# DAC.net
KiCad netlist of a schematic drawn in Altium Designer
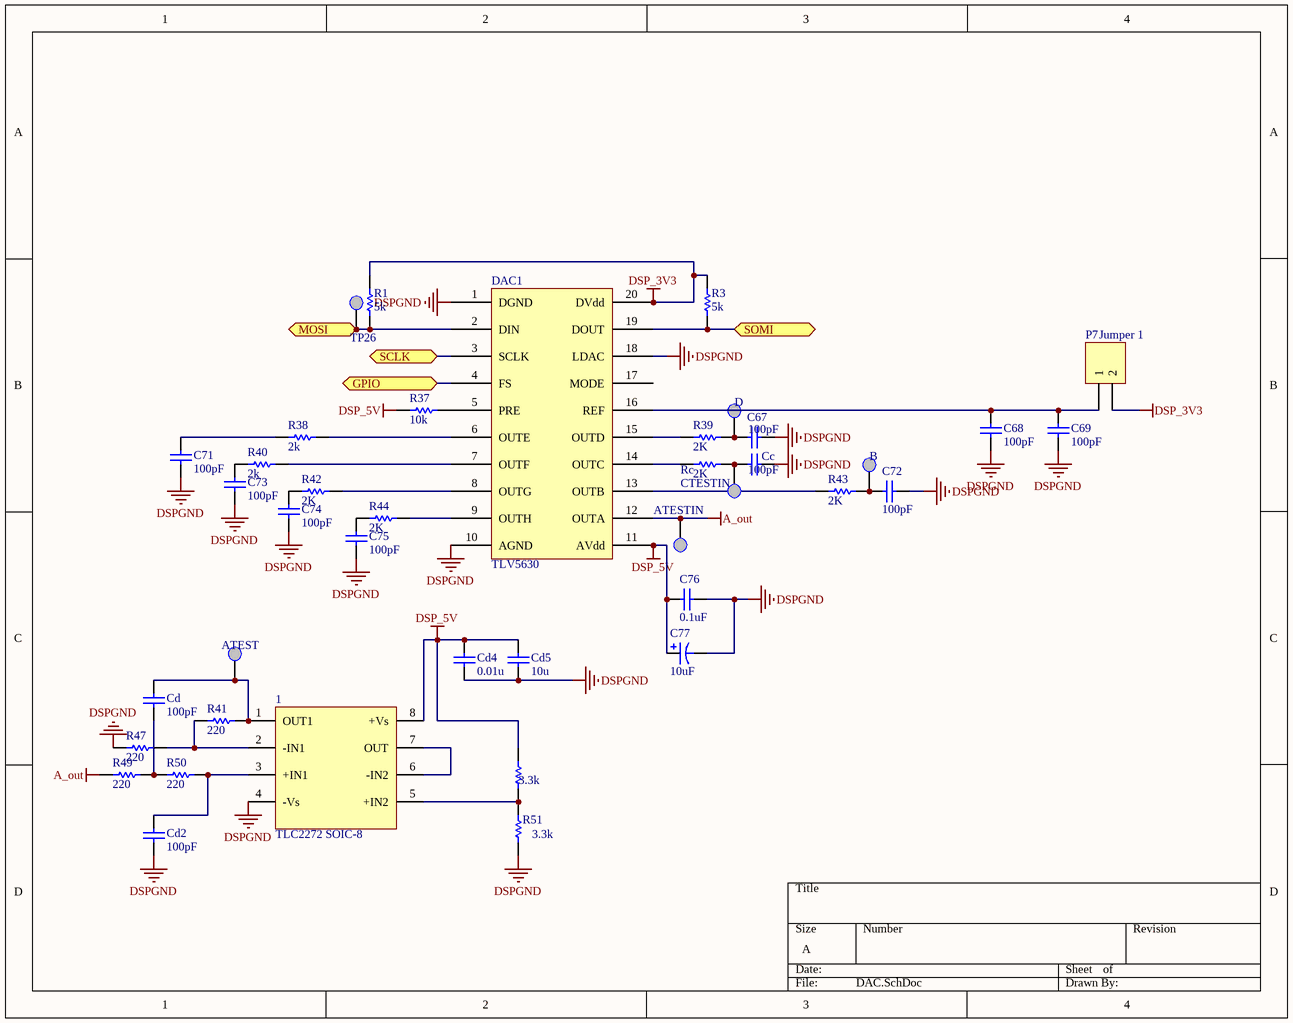
[diagram p0: DAC.SchDoc]

(export (version "E")
  (design (tool "Eeschema 10.0.6"))
  (components
    (comp (ref "1")
      (value "TLC2272 SOIC-8")
      (footprint "AD8056")
      (libsource (lib "control Board") (part "AD8056"))
    )
    (comp (ref "3.3k")
      (value "Res1")
      (footprint "0805 RES")
      (description "Resistor")
      (fields (field (name "PUBLISHER") "Altium Limited"))
      (libsource (lib "control Board") (part "Res1"))
    )
    (comp (ref "ATEST")
      (value "Test point")
      (footprint "Test Point")
      (libsource (lib "control Board") (part "Test point"))
    )
    (comp (ref "ATESTIN")
      (value "Test point")
      (footprint "Test Point")
      (libsource (lib "control Board") (part "Test point"))
    )
    (comp (ref "B")
      (value "Test point")
      (footprint "Test Point")
      (libsource (lib "control Board") (part "Test point"))
    )
    (comp (ref "C67")
      (value "100pF")
      (footprint "Capacitor 0805")
      (description "Capacitor")
      (fields (field (name "Comment") "Cap") (field (name "PUBLISHER") "Altium Limited"))
      (libsource (lib "Miscellaneous Devices") (part "Cap"))
    )
    (comp (ref "C68")
      (value "100pF")
      (footprint "Capacitor 0805")
      (description "Capacitor")
      (fields (field (name "Comment") "Cap") (field (name "PUBLISHER") "Altium Limited"))
      (libsource (lib "Miscellaneous Devices") (part "Cap"))
    )
    (comp (ref "C69")
      (value "100pF")
      (footprint "Capacitor 0805")
      (description "Capacitor")
      (fields (field (name "Comment") "Cap") (field (name "PUBLISHER") "Altium Limited"))
      (libsource (lib "Miscellaneous Devices") (part "Cap"))
    )
    (comp (ref "C71")
      (value "100pF")
      (footprint "Capacitor 0805")
      (description "Capacitor")
      (fields (field (name "Comment") "Cap") (field (name "PUBLISHER") "Altium Limited"))
      (libsource (lib "Miscellaneous Devices") (part "Cap"))
    )
    (comp (ref "C72")
      (value "100pF")
      (footprint "Capacitor 0805")
      (description "Capacitor")
      (fields (field (name "Comment") "Cap") (field (name "PUBLISHER") "Altium Limited"))
      (libsource (lib "Miscellaneous Devices") (part "Cap"))
    )
    (comp (ref "C73")
      (value "100pF")
      (footprint "Capacitor 0805")
      (description "Capacitor")
      (fields (field (name "Comment") "Cap") (field (name "PUBLISHER") "Altium Limited"))
      (libsource (lib "Miscellaneous Devices") (part "Cap"))
    )
    (comp (ref "C74")
      (value "100pF")
      (footprint "Capacitor 0805")
      (description "Capacitor")
      (fields (field (name "Comment") "Cap") (field (name "PUBLISHER") "Altium Limited"))
      (libsource (lib "Miscellaneous Devices") (part "Cap"))
    )
    (comp (ref "C75")
      (value "100pF")
      (footprint "Capacitor 0805")
      (description "Capacitor")
      (fields (field (name "Comment") "Cap") (field (name "PUBLISHER") "Altium Limited"))
      (libsource (lib "Miscellaneous Devices") (part "Cap"))
    )
    (comp (ref "C76")
      (value "0.1uF")
      (footprint "Capacitor 0805")
      (description "Capacitor")
      (fields (field (name "Comment") "Cap") (field (name "PUBLISHER") "Altium Limited"))
      (libsource (lib "Miscellaneous Devices") (part "Cap"))
    )
    (comp (ref "C77")
      (value "10uF")
      (footprint "Cap Tantal 3216")
      (description "Polarized Capacitor (Radial)")
      (fields
        (field (name "Comment") "Tantalium/T520A226M006ATE090")
        (field (name "PUBLISHER") "Altium Limited")
      )
      (libsource (lib "Miscellaneous Devices") (part "Cap Pol1"))
    )
    (comp (ref "Cc")
      (value "100pF")
      (footprint "Capacitor 0805")
      (description "Capacitor")
      (fields (field (name "Comment") "Cap") (field (name "PUBLISHER") "Altium Limited"))
      (libsource (lib "Miscellaneous Devices") (part "Cap"))
    )
    (comp (ref "Cd")
      (value "100pF")
      (footprint "Capacitor 0805")
      (description "Capacitor")
      (fields (field (name "Comment") "Cap") (field (name "PUBLISHER") "Altium Limited"))
      (libsource (lib "Miscellaneous Devices") (part "Cap"))
    )
    (comp (ref "Cd2")
      (value "100pF")
      (footprint "Capacitor 0805")
      (description "Capacitor")
      (fields (field (name "Comment") "Cap") (field (name "PUBLISHER") "Altium Limited"))
      (libsource (lib "Miscellaneous Devices") (part "Cap"))
    )
    (comp (ref "Cd4")
      (value "0.01u")
      (footprint "Capacitor 0805")
      (description "Capacitor")
      (fields (field (name "Comment") "Cap") (field (name "PUBLISHER") "Altium Limited"))
      (libsource (lib "Miscellaneous Devices") (part "Cap"))
    )
    (comp (ref "Cd5")
      (value "10u")
      (footprint "Capacitor 0805")
      (description "Capacitor")
      (fields (field (name "Comment") "Cap") (field (name "PUBLISHER") "Altium Limited"))
      (libsource (lib "Miscellaneous Devices") (part "Cap"))
    )
    (comp (ref "CTESTIN")
      (value "Test point")
      (footprint "Test Point")
      (libsource (lib "control Board") (part "Test point"))
    )
    (comp (ref "D")
      (value "Test point")
      (footprint "Test Point")
      (libsource (lib "control Board") (part "Test point"))
    )
    (comp (ref "DAC1")
      (value "TLV5630")
      (footprint "TLV5630")
      (libsource (lib "control Board") (part "TLV5630"))
    )
    (comp (ref "P7")
      (value "Jumper 1")
      (footprint "HDR1X2")
      (description "Header, 2-Pin")
      (fields (field (name "PUBLISHER") "Altium Limited"))
      (libsource (lib "Miscellaneous Connectors") (part "Header 2"))
    )
    (comp (ref "R1")
      (value "5k")
      (footprint "0805 RES")
      (description "Resistor")
      (fields (field (name "Comment") "Res1") (field (name "PUBLISHER") "Altium Limited"))
      (libsource (lib "control Board") (part "Res1"))
    )
    (comp (ref "R3")
      (value "5k")
      (footprint "0805 RES")
      (description "Resistor")
      (fields (field (name "Comment") "Res1") (field (name "PUBLISHER") "Altium Limited"))
      (libsource (lib "control Board") (part "Res1"))
    )
    (comp (ref "R37")
      (value "10k")
      (footprint "0805 RES")
      (description "Resistor")
      (fields (field (name "Comment") "Res1") (field (name "PUBLISHER") "Altium Limited"))
      (libsource (lib "control Board") (part "Res1"))
    )
    (comp (ref "R38")
      (value "2k")
      (footprint "0805 RES")
      (description "Resistor")
      (fields (field (name "Comment") "Res1") (field (name "PUBLISHER") "Altium Limited"))
      (libsource (lib "control Board") (part "Res1"))
    )
    (comp (ref "R39")
      (value "2K")
      (footprint "0805 RES")
      (description "Resistor")
      (fields (field (name "Comment") "Res1") (field (name "PUBLISHER") "Altium Limited"))
      (libsource (lib "control Board") (part "Res1"))
    )
    (comp (ref "R40")
      (value "2k")
      (footprint "0805 RES")
      (description "Resistor")
      (fields (field (name "Comment") "Res1") (field (name "PUBLISHER") "Altium Limited"))
      (libsource (lib "control Board") (part "Res1"))
    )
    (comp (ref "R41")
      (value "220")
      (footprint "0805 RES")
      (description "Resistor")
      (fields (field (name "Comment") "Res1") (field (name "PUBLISHER") "Altium Limited"))
      (libsource (lib "control Board") (part "Res1"))
    )
    (comp (ref "R42")
      (value "2K")
      (footprint "0805 RES")
      (description "Resistor")
      (fields (field (name "Comment") "Res1") (field (name "PUBLISHER") "Altium Limited"))
      (libsource (lib "control Board") (part "Res1"))
    )
    (comp (ref "R43")
      (value "2K")
      (footprint "0805 RES")
      (description "Resistor")
      (fields (field (name "Comment") "Res1") (field (name "PUBLISHER") "Altium Limited"))
      (libsource (lib "control Board") (part "Res1"))
    )
    (comp (ref "R44")
      (value "2K")
      (footprint "0805 RES")
      (description "Resistor")
      (fields (field (name "Comment") "Res1") (field (name "PUBLISHER") "Altium Limited"))
      (libsource (lib "control Board") (part "Res1"))
    )
    (comp (ref "R47")
      (value "220")
      (footprint "0805 RES")
      (description "Resistor")
      (fields (field (name "Comment") "Res1") (field (name "PUBLISHER") "Altium Limited"))
      (libsource (lib "control Board") (part "Res1"))
    )
    (comp (ref "R49")
      (value "220")
      (footprint "0805 RES")
      (description "Resistor")
      (fields (field (name "Comment") "Res1") (field (name "PUBLISHER") "Altium Limited"))
      (libsource (lib "control Board") (part "Res1"))
    )
    (comp (ref "R50")
      (value "220")
      (footprint "0805 RES")
      (description "Resistor")
      (fields (field (name "Comment") "Res1") (field (name "PUBLISHER") "Altium Limited"))
      (libsource (lib "control Board") (part "Res1"))
    )
    (comp (ref "R51")
      (value "3.3k")
      (footprint "0805 RES")
      (description "Resistor")
      (fields (field (name "Comment") "Res1") (field (name "PUBLISHER") "Altium Limited"))
      (libsource (lib "control Board") (part "Res1"))
    )
    (comp (ref "Rc")
      (value "2K")
      (footprint "0805 RES")
      (description "Resistor")
      (fields (field (name "Comment") "Res1") (field (name "PUBLISHER") "Altium Limited"))
      (libsource (lib "control Board") (part "Res1"))
    )
    (comp (ref "TP26")
      (value "Test point")
      (footprint "Test Point")
      (libsource (lib "control Board") (part "Test point"))
    )
  )
  (nets
    (net (code "1") (name "/GPIO") (class "Default")
      (node (ref "DAC1") (pin "4") (pinfunction "FS_4") (pintype "passive"))
    )
    (net (code "2") (name "/MOSI") (class "Default")
      (node (ref "DAC1") (pin "2") (pinfunction "DIN_2") (pintype "passive"))
      (node (ref "R1") (pin "1") (pinfunction "1_1") (pintype "passive"))
      (node (ref "TP26") (pin "1") (pintype "passive"))
    )
    (net (code "3") (name "/SCLK") (class "Default")
      (node (ref "DAC1") (pin "3") (pinfunction "SCLK_3") (pintype "passive"))
    )
    (net (code "4") (name "/SOMI") (class "Default")
      (node (ref "DAC1") (pin "19") (pinfunction "DOUT_19") (pintype "passive"))
      (node (ref "R3") (pin "1") (pinfunction "1_1") (pintype "passive"))
    )
    (net (code "5") (name "A_out") (class "Default")
      (node (ref "ATESTIN") (pin "1") (pintype "passive"))
      (node (ref "DAC1") (pin "12") (pinfunction "OUTA_12") (pintype "passive"))
      (node (ref "R49") (pin "1") (pinfunction "1_1") (pintype "passive"))
    )
    (net (code "6") (name "DSPGND") (class "Default")
      (node (ref "1") (pin "4") (pinfunction "-Vs_4") (pintype "passive"))
      (node (ref "C67") (pin "2") (pinfunction "2_2") (pintype "passive"))
      (node (ref "C68") (pin "2") (pinfunction "2_2") (pintype "passive"))
      (node (ref "C69") (pin "2") (pinfunction "2_2") (pintype "passive"))
      (node (ref "C71") (pin "2") (pinfunction "2_2") (pintype "passive"))
      (node (ref "C72") (pin "2") (pinfunction "2_2") (pintype "passive"))
      (node (ref "C73") (pin "2") (pinfunction "2_2") (pintype "passive"))
      (node (ref "C74") (pin "2") (pinfunction "2_2") (pintype "passive"))
      (node (ref "C75") (pin "2") (pinfunction "2_2") (pintype "passive"))
      (node (ref "C76") (pin "1") (pinfunction "1_1") (pintype "passive"))
      (node (ref "C77") (pin "2") (pinfunction "2_2") (pintype "passive"))
      (node (ref "Cc") (pin "2") (pinfunction "2_2") (pintype "passive"))
      (node (ref "Cd2") (pin "2") (pinfunction "2_2") (pintype "passive"))
      (node (ref "Cd4") (pin "2") (pinfunction "2_2") (pintype "passive"))
      (node (ref "Cd5") (pin "2") (pinfunction "2_2") (pintype "passive"))
      (node (ref "DAC1") (pin "1") (pinfunction "DGND_1") (pintype "passive"))
      (node (ref "DAC1") (pin "10") (pinfunction "AGND_10") (pintype "passive"))
      (node (ref "DAC1") (pin "18") (pinfunction "LDAC_18") (pintype "passive"))
      (node (ref "R47") (pin "1") (pinfunction "1_1") (pintype "passive"))
      (node (ref "R51") (pin "1") (pinfunction "1_1") (pintype "passive"))
    )
    (net (code "7") (name "DSP_3V3") (class "Default")
      (node (ref "DAC1") (pin "20") (pinfunction "DVdd_20") (pintype "passive"))
      (node (ref "P7") (pin "2") (pinfunction "2_2") (pintype "passive"))
      (node (ref "R1") (pin "2") (pinfunction "2_2") (pintype "passive"))
      (node (ref "R3") (pin "2") (pinfunction "2_2") (pintype "passive"))
    )
    (net (code "8") (name "DSP_5V") (class "Default")
      (node (ref "1") (pin "8") (pinfunction "+Vs_8") (pintype "passive"))
      (node (ref "3.3k") (pin "2") (pinfunction "2_2") (pintype "passive"))
      (node (ref "C76") (pin "2") (pinfunction "2_2") (pintype "passive"))
      (node (ref "C77") (pin "1") (pinfunction "1_1") (pintype "passive"))
      (node (ref "Cd4") (pin "1") (pinfunction "1_1") (pintype "passive"))
      (node (ref "Cd5") (pin "1") (pinfunction "1_1") (pintype "passive"))
      (node (ref "DAC1") (pin "11") (pinfunction "AVdd_11") (pintype "passive"))
      (node (ref "R37") (pin "1") (pinfunction "1_1") (pintype "passive"))
    )
    (net (code "9") (name "Net-(1-+IN1)") (class "Default")
      (node (ref "1") (pin "3") (pinfunction "+IN1_3") (pintype "passive"))
      (node (ref "Cd2") (pin "1") (pinfunction "1_1") (pintype "passive"))
      (node (ref "R50") (pin "2") (pinfunction "2_2") (pintype "passive"))
    )
    (net (code "10") (name "Net-(1-+IN2)") (class "Default")
      (node (ref "1") (pin "5") (pinfunction "+IN2_5") (pintype "passive"))
      (node (ref "3.3k") (pin "1") (pinfunction "1_1") (pintype "passive"))
      (node (ref "R51") (pin "2") (pinfunction "2_2") (pintype "passive"))
    )
    (net (code "11") (name "Net-(1--IN1)") (class "Default")
      (node (ref "1") (pin "2") (pinfunction "-IN1_2") (pintype "passive"))
      (node (ref "R41") (pin "1") (pinfunction "1_1") (pintype "passive"))
      (node (ref "R47") (pin "2") (pinfunction "2_2") (pintype "passive"))
    )
    (net (code "12") (name "Net-(1--IN2)") (class "Default")
      (node (ref "1") (pin "6") (pinfunction "-IN2_6") (pintype "passive"))
      (node (ref "1") (pin "7") (pinfunction "OUT_7") (pintype "passive"))
    )
    (net (code "13") (name "Net-(1-OUT1)") (class "Default")
      (node (ref "1") (pin "1") (pinfunction "OUT1_1") (pintype "passive"))
      (node (ref "ATEST") (pin "1") (pintype "passive"))
      (node (ref "Cd") (pin "1") (pinfunction "1_1") (pintype "passive"))
      (node (ref "R41") (pin "2") (pinfunction "2_2") (pintype "passive"))
    )
    (net (code "14") (name "Net-(B-Pad1)") (class "Default")
      (node (ref "B") (pin "1") (pintype "passive"))
      (node (ref "C72") (pin "1") (pinfunction "1_1") (pintype "passive"))
      (node (ref "R43") (pin "2") (pinfunction "2_2") (pintype "passive"))
    )
    (net (code "15") (name "Net-(C67-Pad1)") (class "Default")
      (node (ref "C67") (pin "1") (pinfunction "1_1") (pintype "passive"))
      (node (ref "D") (pin "1") (pintype "passive"))
      (node (ref "R39") (pin "2") (pinfunction "2_2") (pintype "passive"))
    )
    (net (code "16") (name "Net-(C71-Pad1)") (class "Default")
      (node (ref "C71") (pin "1") (pinfunction "1_1") (pintype "passive"))
      (node (ref "R38") (pin "1") (pinfunction "1_1") (pintype "passive"))
    )
    (net (code "17") (name "Net-(C73-Pad1)") (class "Default")
      (node (ref "C73") (pin "1") (pinfunction "1_1") (pintype "passive"))
      (node (ref "R40") (pin "1") (pinfunction "1_1") (pintype "passive"))
    )
    (net (code "18") (name "Net-(C74-Pad1)") (class "Default")
      (node (ref "C74") (pin "1") (pinfunction "1_1") (pintype "passive"))
      (node (ref "R42") (pin "2") (pinfunction "2_2") (pintype "passive"))
    )
    (net (code "19") (name "Net-(C75-Pad1)") (class "Default")
      (node (ref "C75") (pin "1") (pinfunction "1_1") (pintype "passive"))
      (node (ref "R44") (pin "2") (pinfunction "2_2") (pintype "passive"))
    )
    (net (code "20") (name "Net-(CTESTIN-Pad1)") (class "Default")
      (node (ref "CTESTIN") (pin "1") (pintype "passive"))
      (node (ref "Cc") (pin "1") (pinfunction "1_1") (pintype "passive"))
      (node (ref "Rc") (pin "2") (pinfunction "2_2") (pintype "passive"))
    )
    (net (code "21") (name "Net-(Cd-Pad2)") (class "Default")
      (node (ref "Cd") (pin "2") (pinfunction "2_2") (pintype "passive"))
      (node (ref "R49") (pin "2") (pinfunction "2_2") (pintype "passive"))
      (node (ref "R50") (pin "1") (pinfunction "1_1") (pintype "passive"))
    )
    (net (code "22") (name "Net-(DAC1-OUTB)") (class "Default")
      (node (ref "DAC1") (pin "13") (pinfunction "OUTB_13") (pintype "passive"))
      (node (ref "R43") (pin "1") (pinfunction "1_1") (pintype "passive"))
    )
    (net (code "23") (name "Net-(DAC1-OUTC)") (class "Default")
      (node (ref "DAC1") (pin "14") (pinfunction "OUTC_14") (pintype "passive"))
      (node (ref "Rc") (pin "1") (pinfunction "1_1") (pintype "passive"))
    )
    (net (code "24") (name "Net-(DAC1-OUTD)") (class "Default")
      (node (ref "DAC1") (pin "15") (pinfunction "OUTD_15") (pintype "passive"))
      (node (ref "R39") (pin "1") (pinfunction "1_1") (pintype "passive"))
    )
    (net (code "25") (name "Net-(DAC1-OUTE)") (class "Default")
      (node (ref "DAC1") (pin "6") (pinfunction "OUTE_6") (pintype "passive"))
      (node (ref "R38") (pin "2") (pinfunction "2_2") (pintype "passive"))
    )
    (net (code "26") (name "Net-(DAC1-OUTF)") (class "Default")
      (node (ref "DAC1") (pin "7") (pinfunction "OUTF_7") (pintype "passive"))
      (node (ref "R40") (pin "2") (pinfunction "2_2") (pintype "passive"))
    )
    (net (code "27") (name "Net-(DAC1-OUTG)") (class "Default")
      (node (ref "DAC1") (pin "8") (pinfunction "OUTG_8") (pintype "passive"))
      (node (ref "R42") (pin "1") (pinfunction "1_1") (pintype "passive"))
    )
    (net (code "28") (name "Net-(DAC1-OUTH)") (class "Default")
      (node (ref "DAC1") (pin "9") (pinfunction "OUTH_9") (pintype "passive"))
      (node (ref "R44") (pin "1") (pinfunction "1_1") (pintype "passive"))
    )
    (net (code "29") (name "Net-(DAC1-PRE)") (class "Default")
      (node (ref "DAC1") (pin "5") (pinfunction "PRE_5") (pintype "passive"))
      (node (ref "R37") (pin "2") (pinfunction "2_2") (pintype "passive"))
    )
    (net (code "30") (name "Net-(DAC1-REF)") (class "Default")
      (node (ref "C68") (pin "1") (pinfunction "1_1") (pintype "passive"))
      (node (ref "C69") (pin "1") (pinfunction "1_1") (pintype "passive"))
      (node (ref "DAC1") (pin "16") (pinfunction "REF_16") (pintype "passive"))
      (node (ref "P7") (pin "1") (pinfunction "1_1") (pintype "passive"))
    )
    (net (code "31") (name "unconnected-(DAC1-MODE-Pad17)") (class "Default")
      (node (ref "DAC1") (pin "17") (pinfunction "MODE_17") (pintype "passive"))
    )
  )
)
